# source_eagle.net
KiCad netlist of a schematic drawn in EAGLE
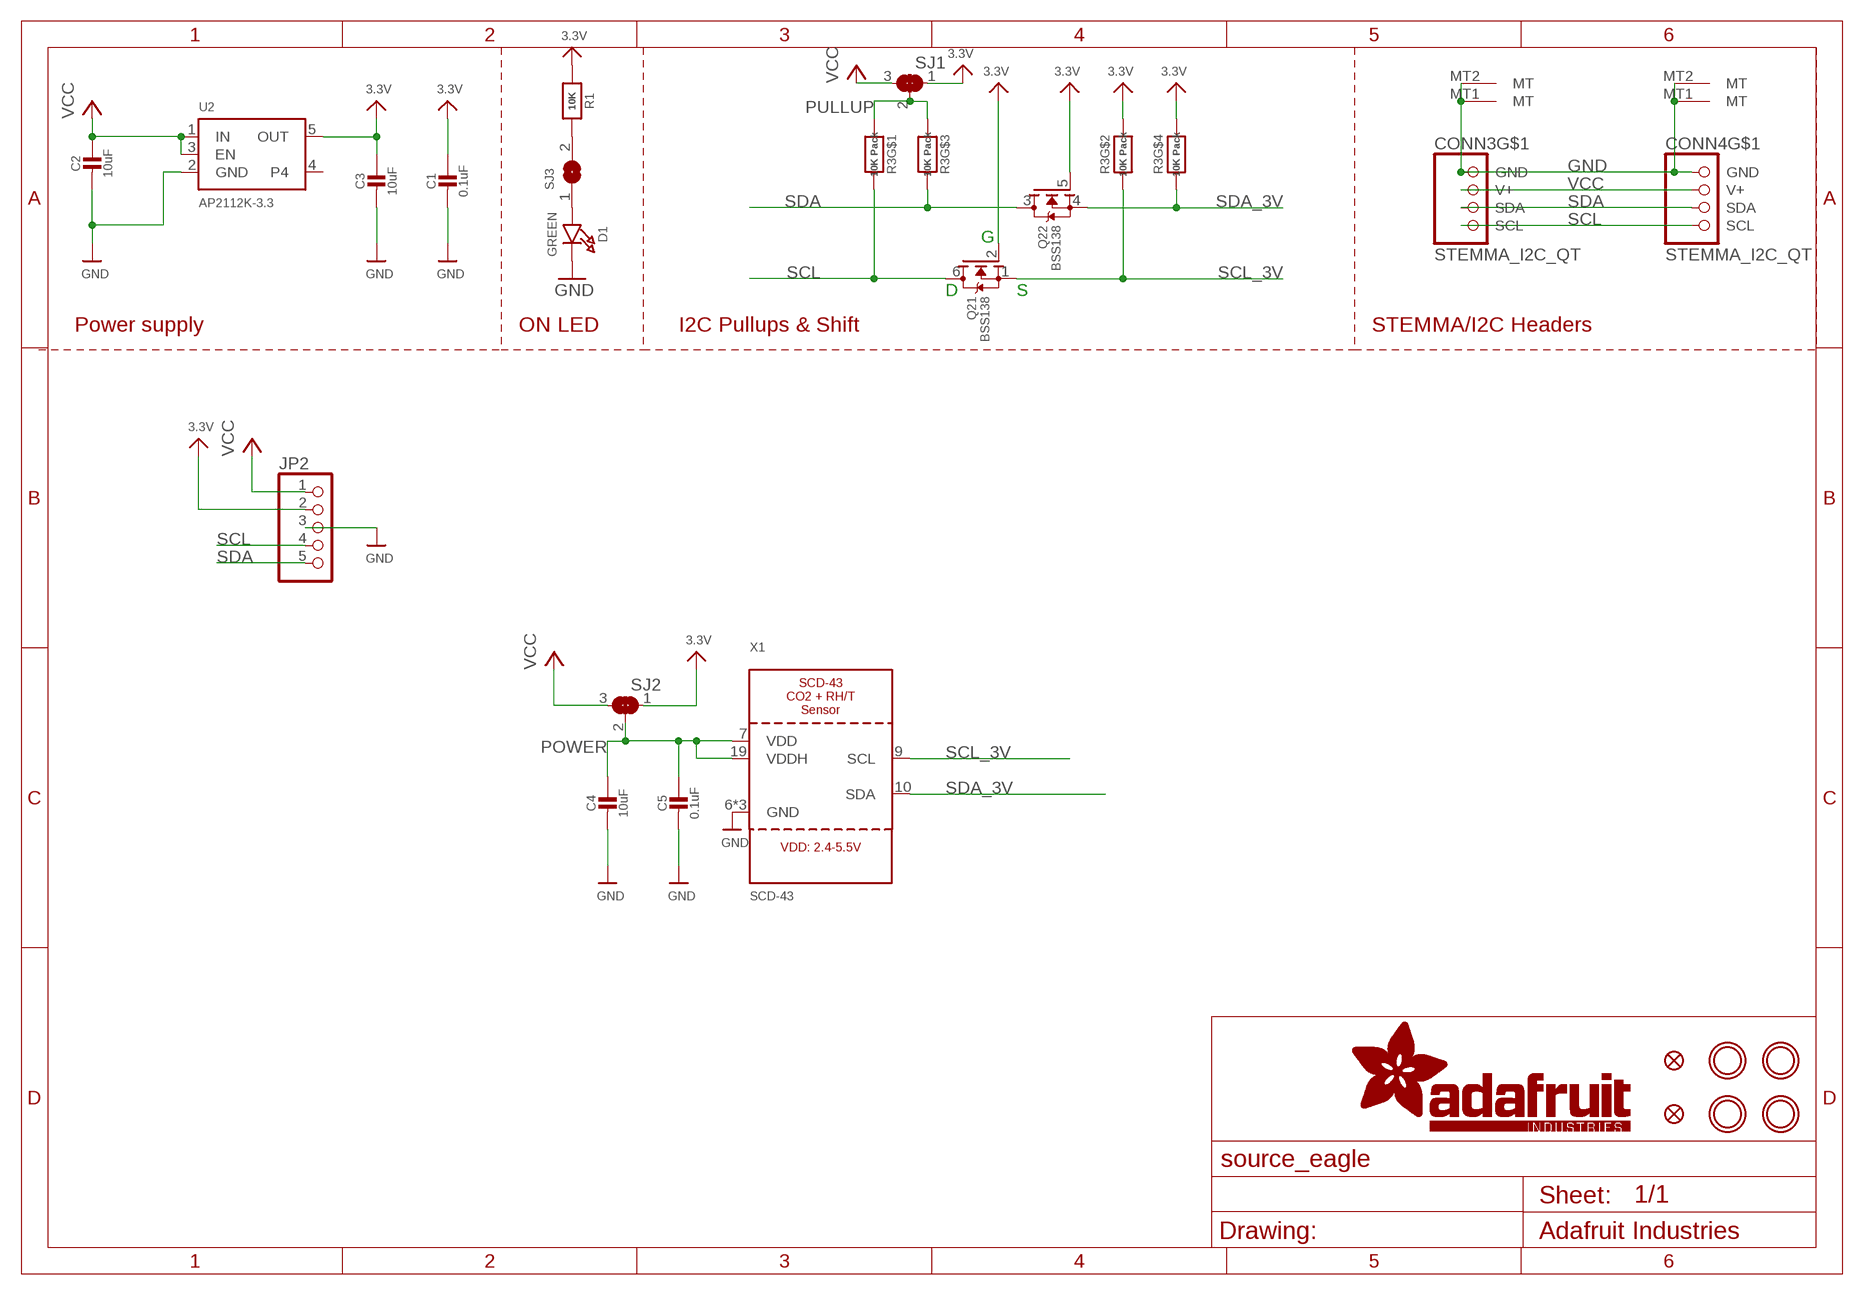
[diagram p0: schematic, sheet 1]

(export (version "E")
  (design (tool "Eeschema 10.0.6"))
  (components
    (comp (ref "C1")
      (value "0.1uF")
      (footprint "eagle-import:0603-NO")
      (libsource (lib "eagle-import") (part "CAP_CERAMIC0603_NO"))
    )
    (comp (ref "C2")
      (value "10uF")
      (footprint "eagle-import:0805-NO")
      (libsource (lib "eagle-import") (part "CAP_CERAMIC0805-NOOUTLINE"))
    )
    (comp (ref "C3")
      (value "10uF")
      (footprint "eagle-import:0805-NO")
      (libsource (lib "eagle-import") (part "CAP_CERAMIC0805-NOOUTLINE"))
    )
    (comp (ref "C4")
      (value "10uF")
      (footprint "eagle-import:0805-NO")
      (libsource (lib "eagle-import") (part "CAP_CERAMIC0805-NOOUTLINE"))
    )
    (comp (ref "C5")
      (value "0.1uF")
      (footprint "eagle-import:0603-NO")
      (libsource (lib "eagle-import") (part "CAP_CERAMIC0603_NO"))
    )
    (comp (ref "CONN3")
      (value "STEMMA_I2C_QT")
      (footprint "eagle-import:JST_SH4")
      (libsource (lib "eagle-import") (part "STEMMA_I2C_QT"))
    )
    (comp (ref "CONN4")
      (value "STEMMA_I2C_QT")
      (footprint "eagle-import:JST_SH4")
      (libsource (lib "eagle-import") (part "STEMMA_I2C_QT"))
    )
    (comp (ref "D1")
      (value "GREEN")
      (footprint "eagle-import:CHIPLED_0603_NOOUTLINE")
      (libsource (lib "eagle-import") (part "LED0603_NOOUTLINE"))
    )
    (comp (ref "FID3")
      (value "FIDUCIAL_1MM")
      (footprint "eagle-import:FIDUCIAL_1MM")
      (libsource (lib "eagle-import") (part "FIDUCIAL_1MM"))
    )
    (comp (ref "FID4")
      (value "FIDUCIAL_1MM")
      (footprint "eagle-import:FIDUCIAL_1MM")
      (libsource (lib "eagle-import") (part "FIDUCIAL_1MM"))
    )
    (comp (ref "JP2")
      (value "HEADER-1X576MIL")
      (footprint "eagle-import:1X05_ROUND_76")
      (libsource (lib "eagle-import") (part "HEADER-1X576MIL"))
    )
    (comp (ref "Q2")
      (value "BSS138")
      (footprint "eagle-import:SOT363")
      (libsource (lib "eagle-import") (part "MOSFET-N_DUAL"))
    )
    (comp (ref "R1")
      (value "10K")
      (footprint "eagle-import:0603-NO")
      (libsource (lib "eagle-import") (part "RESISTOR_0603_NOOUT"))
    )
    (comp (ref "R3")
      (value "10K Pack")
      (footprint "eagle-import:RESPACK_4X0603")
      (libsource (lib "eagle-import") (part "RESISTOR_4PACK"))
    )
    (comp (ref "SJ1")
      (value "SOLDERJUMPER_2WAY")
      (footprint "eagle-import:SOLDERJUMPER_2WAY_OPEN_NOPASTE")
      (libsource (lib "eagle-import") (part "SOLDERJUMPER_2WAY"))
    )
    (comp (ref "SJ2")
      (value "SOLDERJUMPER_2WAY")
      (footprint "eagle-import:SOLDERJUMPER_2WAY_OPEN_NOPASTE")
      (libsource (lib "eagle-import") (part "SOLDERJUMPER_2WAY"))
    )
    (comp (ref "SJ3")
      (value "SOLDERJUMPERCLOSED")
      (footprint "eagle-import:SOLDERJUMPER_CLOSEDWIRE")
      (libsource (lib "eagle-import") (part "SOLDERJUMPERCLOSED"))
    )
    (comp (ref "U$1")
      (value "MOUNTINGHOLE3.0THIN")
      (footprint "eagle-import:MOUNTINGHOLE_3.0_PLATEDTHIN")
      (libsource (lib "eagle-import") (part "MOUNTINGHOLE3.0THIN"))
    )
    (comp (ref "U$17")
      (value "MOUNTINGHOLE3.0THIN")
      (footprint "eagle-import:MOUNTINGHOLE_3.0_PLATEDTHIN")
      (libsource (lib "eagle-import") (part "MOUNTINGHOLE3.0THIN"))
    )
    (comp (ref "U$19")
      (value "MOUNTINGHOLE3.0THIN")
      (footprint "eagle-import:MOUNTINGHOLE_3.0_PLATEDTHIN")
      (libsource (lib "eagle-import") (part "MOUNTINGHOLE3.0THIN"))
    )
    (comp (ref "U$21")
      (value "MOUNTINGHOLE3.0THIN")
      (footprint "eagle-import:MOUNTINGHOLE_3.0_PLATEDTHIN")
      (libsource (lib "eagle-import") (part "MOUNTINGHOLE3.0THIN"))
    )
    (comp (ref "U2")
      (value "AP2112K-3.3")
      (footprint "eagle-import:SOT23-5")
      (fields (field (name "JLC_ROTATION") "0"))
      (libsource (lib "eagle-import") (part "VREG_SOT23-5"))
    )
    (comp (ref "X1")
      (value "SCD-43")
      (footprint "eagle-import:SCD41")
      (libsource (lib "eagle-import") (part "SCD-43"))
    )
  )
  (nets
    (net (code "1") (name "/POWER") (class "Default")
      (node (ref "C4") (pin "1") (pinfunction "1_1") (pintype "passive"))
      (node (ref "C5") (pin "1") (pinfunction "1_1") (pintype "passive"))
      (node (ref "SJ2") (pin "2") (pinfunction "2_2") (pintype "passive"))
      (node (ref "X1") (pin "19") (pinfunction "VDDH_19") (pintype "power_in"))
      (node (ref "X1") (pin "7") (pinfunction "VDD_7") (pintype "power_in"))
    )
    (net (code "2") (name "/PULLUP") (class "Default")
      (node (ref "R3") (pin "1") (pinfunction "1_1") (pintype "passive"))
      (node (ref "R3") (pin "3") (pinfunction "1_3") (pintype "passive"))
      (node (ref "SJ1") (pin "2") (pinfunction "2_2") (pintype "passive"))
    )
    (net (code "3") (name "/SCL") (class "Default")
      (node (ref "CONN3") (pin "4") (pinfunction "SCL_4") (pintype "passive"))
      (node (ref "CONN4") (pin "4") (pinfunction "SCL_4") (pintype "passive"))
      (node (ref "JP2") (pin "4") (pinfunction "4_4") (pintype "passive"))
      (node (ref "Q2") (pin "6") (pinfunction "D_6") (pintype "bidirectional"))
      (node (ref "R3") (pin "8") (pinfunction "2_8") (pintype "passive"))
    )
    (net (code "4") (name "/SCL_3V") (class "Default")
      (node (ref "Q2") (pin "1") (pinfunction "S_1") (pintype "bidirectional"))
      (node (ref "R3") (pin "7") (pinfunction "2_7") (pintype "passive"))
      (node (ref "X1") (pin "9") (pinfunction "SCL_9") (pintype "input"))
    )
    (net (code "5") (name "/SDA") (class "Default")
      (node (ref "CONN3") (pin "3") (pinfunction "SDA_3") (pintype "passive"))
      (node (ref "CONN4") (pin "3") (pinfunction "SDA_3") (pintype "passive"))
      (node (ref "JP2") (pin "5") (pinfunction "5_5") (pintype "passive"))
      (node (ref "Q2") (pin "3") (pinfunction "D_3") (pintype "bidirectional"))
      (node (ref "R3") (pin "6") (pinfunction "2_6") (pintype "passive"))
    )
    (net (code "6") (name "/SDA_3V") (class "Default")
      (node (ref "Q2") (pin "4") (pinfunction "S_4") (pintype "bidirectional"))
      (node (ref "R3") (pin "5") (pinfunction "2_5") (pintype "passive"))
      (node (ref "X1") (pin "10") (pinfunction "SDA_10") (pintype "bidirectional"))
    )
    (net (code "7") (name "3.3V") (class "Default")
      (node (ref "C1") (pin "1") (pinfunction "1_1") (pintype "passive"))
      (node (ref "C3") (pin "1") (pinfunction "1_1") (pintype "passive"))
      (node (ref "JP2") (pin "2") (pinfunction "2_2") (pintype "passive"))
      (node (ref "Q2") (pin "2") (pinfunction "G_2") (pintype "bidirectional"))
      (node (ref "Q2") (pin "5") (pinfunction "G_5") (pintype "bidirectional"))
      (node (ref "R1") (pin "1") (pinfunction "1_1") (pintype "passive"))
      (node (ref "R3") (pin "2") (pinfunction "1_2") (pintype "passive"))
      (node (ref "R3") (pin "4") (pinfunction "1_4") (pintype "passive"))
      (node (ref "SJ1") (pin "1") (pinfunction "1_1") (pintype "passive"))
      (node (ref "SJ2") (pin "1") (pinfunction "1_1") (pintype "passive"))
      (node (ref "U2") (pin "5") (pinfunction "OUT_5") (pintype "power_in"))
    )
    (net (code "8") (name "GND") (class "Default")
      (node (ref "C1") (pin "2") (pinfunction "2_2") (pintype "passive"))
      (node (ref "C2") (pin "2") (pinfunction "2_2") (pintype "passive"))
      (node (ref "C3") (pin "2") (pinfunction "2_2") (pintype "passive"))
      (node (ref "C4") (pin "2") (pinfunction "2_2") (pintype "passive"))
      (node (ref "C5") (pin "2") (pinfunction "2_2") (pintype "passive"))
      (node (ref "CONN3") (pin "1") (pinfunction "GND_1") (pintype "passive"))
      (node (ref "CONN3") (pin "MT1") (pinfunction "MT_MT1") (pintype "bidirectional"))
      (node (ref "CONN3") (pin "MT2") (pinfunction "MT_MT2") (pintype "bidirectional"))
      (node (ref "CONN4") (pin "1") (pinfunction "GND_1") (pintype "passive"))
      (node (ref "CONN4") (pin "MT1") (pinfunction "MT_MT1") (pintype "bidirectional"))
      (node (ref "CONN4") (pin "MT2") (pinfunction "MT_MT2") (pintype "bidirectional"))
      (node (ref "D1") (pin "C") (pinfunction "C_C") (pintype "passive"))
      (node (ref "JP2") (pin "3") (pinfunction "3_3") (pintype "passive"))
      (node (ref "U2") (pin "2") (pinfunction "GND_2") (pintype "power_in"))
      (node (ref "X1") (pin "20") (pinfunction "GND_20") (pintype "power_in"))
      (node (ref "X1") (pin "6") (pinfunction "GND_6") (pintype "power_in"))
      (node (ref "X1") (pin "P$1") (pinfunction "GND_P$1") (pintype "power_in"))
    )
    (net (code "9") (name "Net-(D1-PadA)") (class "Default")
      (node (ref "D1") (pin "A") (pinfunction "A_A") (pintype "passive"))
      (node (ref "SJ3") (pin "1") (pinfunction "1_1") (pintype "passive"))
    )
    (net (code "10") (name "Net-(R1-Pad2)") (class "Default")
      (node (ref "R1") (pin "2") (pinfunction "2_2") (pintype "passive"))
      (node (ref "SJ3") (pin "2") (pinfunction "2_2") (pintype "passive"))
    )
    (net (code "11") (name "VCC") (class "Default")
      (node (ref "C2") (pin "1") (pinfunction "1_1") (pintype "passive"))
      (node (ref "CONN3") (pin "2") (pinfunction "V+_2") (pintype "passive"))
      (node (ref "CONN4") (pin "2") (pinfunction "V+_2") (pintype "passive"))
      (node (ref "JP2") (pin "1") (pinfunction "1_1") (pintype "passive"))
      (node (ref "SJ1") (pin "3") (pinfunction "3_3") (pintype "passive"))
      (node (ref "SJ2") (pin "3") (pinfunction "3_3") (pintype "passive"))
      (node (ref "U2") (pin "1") (pinfunction "IN_1") (pintype "power_in"))
      (node (ref "U2") (pin "3") (pinfunction "EN_3") (pintype "input"))
    )
    (net (code "12") (name "unconnected-(U2-P4-Pad4)") (class "Default")
      (node (ref "U2") (pin "4") (pinfunction "P4_4") (pintype "bidirectional"))
    )
  )
)
